# exp7lb.net
KiCad netlist of a schematic drawn in EasyEDA Pro
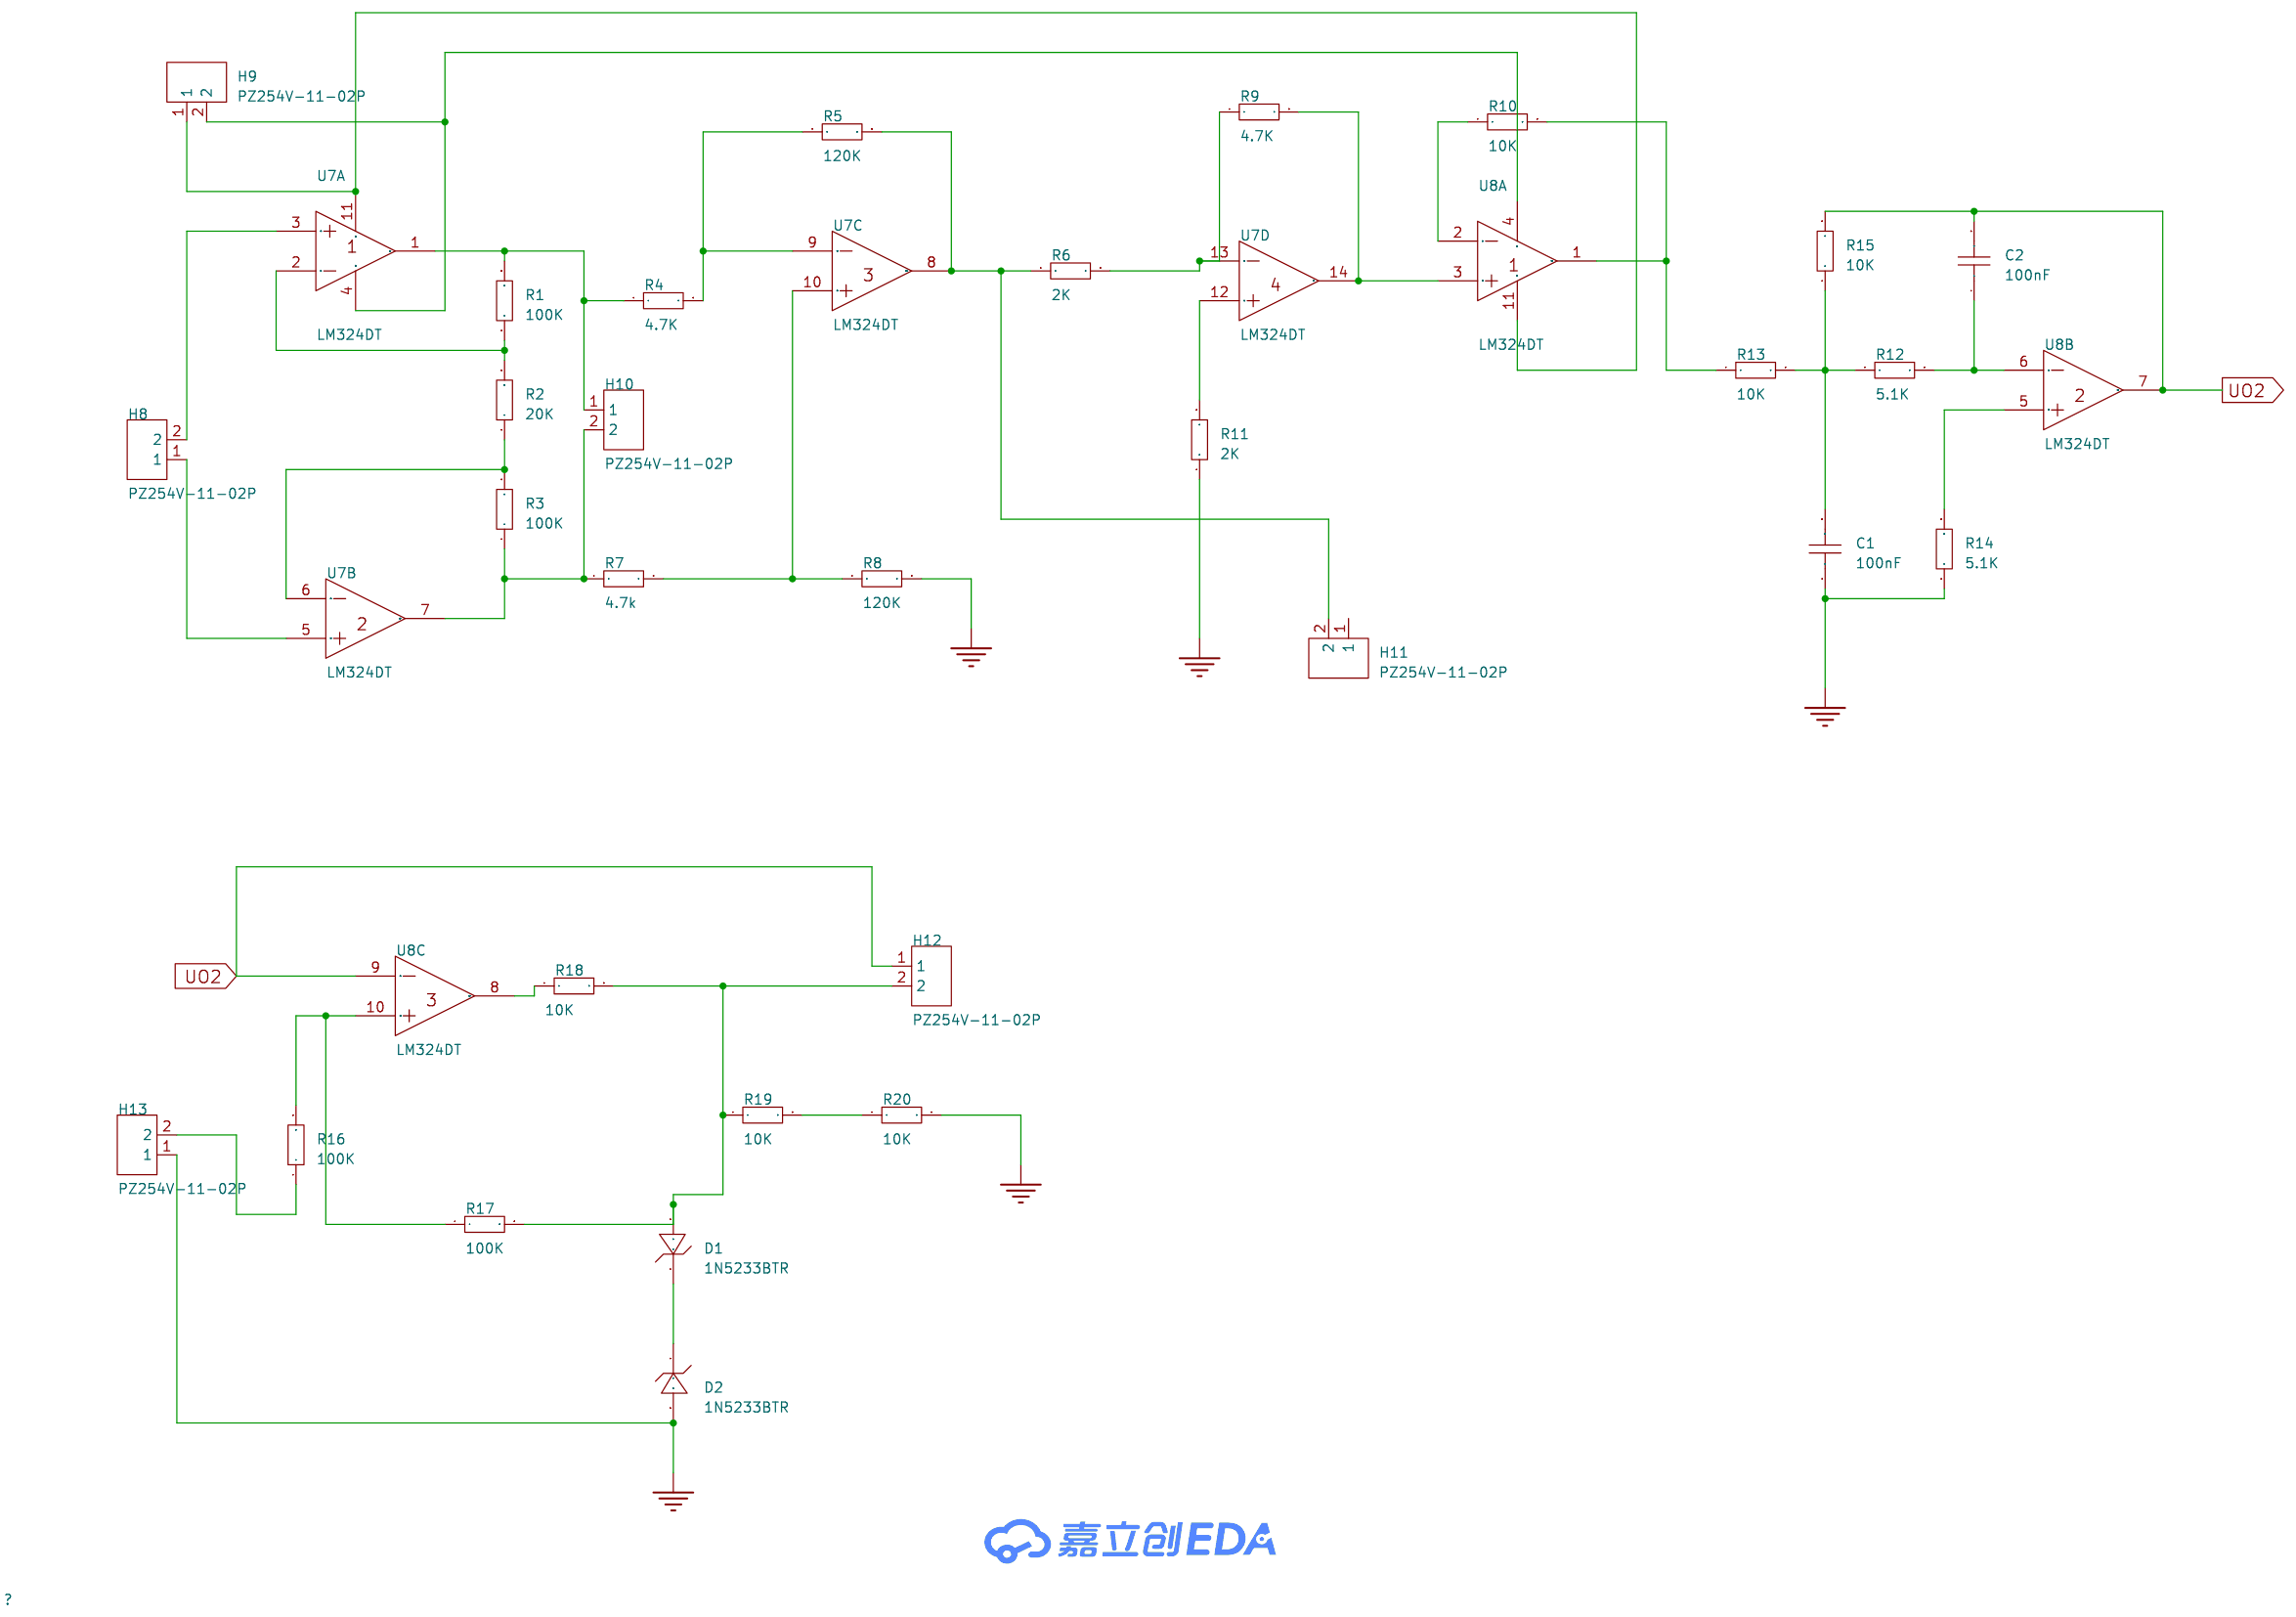
[diagram p0: schematic sheet]

(export (version "E")
  (design (tool "Eeschema 10.0.6"))
  (components
    (comp (ref "C1")
      (value "100nF")
      (footprint "easyedapro:C0603")
      (libsource (lib "easyedapro") (part "Capacitance"))
    )
    (comp (ref "C2")
      (value "100nF")
      (footprint "easyedapro:C0603")
      (libsource (lib "easyedapro") (part "Capacitance"))
    )
    (comp (ref "D1")
      (value "1N5233BTR")
      (footprint "easyedapro:DO-35_BD2.0-L4.2-P8.20-D0.5-RD")
      (description "二极管配置:独立式;稳压值(标称值):6V;稳压值(范围):5.7V~6.3V;耗散功率(Pd):500mW;")
      (fields (field (name "Manufacturer") "onsemi(安森美)"))
      (libsource (lib "easyedapro") (part "1N5233BTR"))
    )
    (comp (ref "D2")
      (value "1N5233BTR")
      (footprint "easyedapro:DO-35_BD2.0-L4.2-P8.20-D0.5-RD")
      (description "二极管配置:独立式;稳压值(标称值):6V;稳压值(范围):5.7V~6.3V;耗散功率(Pd):500mW;")
      (fields (field (name "Manufacturer") "onsemi(安森美)"))
      (libsource (lib "easyedapro") (part "1N5233BTR"))
    )
    (comp (ref "H8")
      (value "PZ254V-11-02P")
      (footprint "easyedapro:HDR-TH_2P-P2.54-V-M")
      (fields (field (name "Manufacturer") "XFCN(兴飞)"))
      (libsource (lib "easyedapro") (part "PZ254V-11-02P"))
    )
    (comp (ref "H9")
      (value "PZ254V-11-02P")
      (footprint "easyedapro:HDR-TH_2P-P2.54-V-M")
      (fields (field (name "Manufacturer") "XFCN(兴飞)"))
      (libsource (lib "easyedapro") (part "PZ254V-11-02P"))
    )
    (comp (ref "H10")
      (value "PZ254V-11-02P")
      (footprint "easyedapro:HDR-TH_2P-P2.54-V-M")
      (fields (field (name "Manufacturer") "XFCN(兴飞)"))
      (libsource (lib "easyedapro") (part "PZ254V-11-02P"))
    )
    (comp (ref "H11")
      (value "PZ254V-11-02P")
      (footprint "easyedapro:HDR-TH_2P-P2.54-V-M")
      (fields (field (name "Manufacturer") "XFCN(兴飞)"))
      (libsource (lib "easyedapro") (part "PZ254V-11-02P"))
    )
    (comp (ref "H12")
      (value "PZ254V-11-02P")
      (footprint "easyedapro:HDR-TH_2P-P2.54-V-M")
      (fields (field (name "Manufacturer") "XFCN(兴飞)"))
      (libsource (lib "easyedapro") (part "PZ254V-11-02P"))
    )
    (comp (ref "H13")
      (value "PZ254V-11-02P")
      (footprint "easyedapro:HDR-TH_2P-P2.54-V-M")
      (fields (field (name "Manufacturer") "XFCN(兴飞)"))
      (libsource (lib "easyedapro") (part "PZ254V-11-02P"))
    )
    (comp (ref "R1") (value "100K") (footprint "easyedapro:R0603") (libsource (lib "easyedapro") (part "电阻")))
    (comp (ref "R2") (value "20K") (footprint "easyedapro:R0603") (libsource (lib "easyedapro") (part "电阻")))
    (comp (ref "R3") (value "100K") (footprint "easyedapro:R0603") (libsource (lib "easyedapro") (part "电阻")))
    (comp (ref "R4") (value "4.7K") (footprint "easyedapro:R0603") (libsource (lib "easyedapro") (part "电阻")))
    (comp (ref "R5") (value "120K") (footprint "easyedapro:R0603") (libsource (lib "easyedapro") (part "电阻")))
    (comp (ref "R6") (value "2K") (footprint "easyedapro:R0603") (libsource (lib "easyedapro") (part "电阻")))
    (comp (ref "R7") (value "4.7k") (footprint "easyedapro:R0603") (libsource (lib "easyedapro") (part "电阻")))
    (comp (ref "R8") (value "120K") (footprint "easyedapro:R0603") (libsource (lib "easyedapro") (part "电阻")))
    (comp (ref "R9") (value "4.7K") (footprint "easyedapro:R0603") (libsource (lib "easyedapro") (part "电阻")))
    (comp (ref "R10") (value "10K") (footprint "easyedapro:R0603") (libsource (lib "easyedapro") (part "电阻")))
    (comp (ref "R11") (value "2K") (footprint "easyedapro:R0603") (libsource (lib "easyedapro") (part "电阻")))
    (comp (ref "R12")
      (value "5.1K")
      (footprint "easyedapro:R0603")
      (libsource (lib "easyedapro") (part "电阻"))
    )
    (comp (ref "R13") (value "10K") (footprint "easyedapro:R0603") (libsource (lib "easyedapro") (part "电阻")))
    (comp (ref "R14")
      (value "5.1K")
      (footprint "easyedapro:R0603")
      (libsource (lib "easyedapro") (part "电阻"))
    )
    (comp (ref "R15") (value "10K") (footprint "easyedapro:R0603") (libsource (lib "easyedapro") (part "电阻")))
    (comp (ref "R16")
      (value "100K")
      (footprint "easyedapro:R0603")
      (libsource (lib "easyedapro") (part "电阻"))
    )
    (comp (ref "R17")
      (value "100K")
      (footprint "easyedapro:R0603")
      (libsource (lib "easyedapro") (part "电阻"))
    )
    (comp (ref "R18") (value "10K") (footprint "easyedapro:R0603") (libsource (lib "easyedapro") (part "电阻")))
    (comp (ref "R19") (value "10K") (footprint "easyedapro:R0603") (libsource (lib "easyedapro") (part "电阻")))
    (comp (ref "R20") (value "10K") (footprint "easyedapro:R0603") (libsource (lib "easyedapro") (part "电阻")))
    (comp (ref "U7")
      (value "LM324DT")
      (footprint "easyedapro:SOIC-14_L8.7-W3.9-P1.27-LS6.0-BL")
      (description "放大器数:四路;轨到轨:-;增益带宽积(GBP):1.3MHz;输入失调电压(Vos):5mV;压摆率(SR):20V/us;输入偏置电流(Ib):300nA;")
      (fields (field (name "Manufacturer") "ST(意法半导体)"))
      (libsource (lib "easyedapro") (part "LM324DT"))
    )
    (comp (ref "U8")
      (value "LM324DT")
      (footprint "easyedapro:SOIC-14_L8.7-W3.9-P1.27-LS6.0-BL")
      (description "放大器数:四路;轨到轨:-;增益带宽积(GBP):1.3MHz;输入失调电压(Vos):5mV;压摆率(SR):20V/us;输入偏置电流(Ib):300nA;")
      (fields (field (name "Manufacturer") "ST(意法半导体)"))
      (libsource (lib "easyedapro") (part "LM324DT"))
    )
  )
  (nets
    (net (code "1") (name "GND") (class "Default")
      (node (ref "C1") (pin "1") (pinfunction "1_1") (pintype "input"))
      (node (ref "D2") (pin "2") (pinfunction "2_2") (pintype "unspecified"))
      (node (ref "H13") (pin "1") (pinfunction "1_1") (pintype "unspecified"))
      (node (ref "R11") (pin "1") (pinfunction "1_1") (pintype "input"))
      (node (ref "R14") (pin "1") (pinfunction "1_1") (pintype "input"))
      (node (ref "R20") (pin "2") (pinfunction "2_2") (pintype "input"))
      (node (ref "R8") (pin "2") (pinfunction "2_2") (pintype "input"))
    )
    (net (code "2") (name "Net-(C1-Pad2)") (class "Default")
      (node (ref "C1") (pin "2") (pinfunction "2_2") (pintype "input"))
      (node (ref "R12") (pin "1") (pinfunction "1_1") (pintype "input"))
      (node (ref "R13") (pin "2") (pinfunction "2_2") (pintype "input"))
      (node (ref "R15") (pin "1") (pinfunction "1_1") (pintype "input"))
    )
    (net (code "3") (name "Net-(D1-Pad1)") (class "Default")
      (node (ref "D1") (pin "1") (pinfunction "1_1") (pintype "unspecified"))
      (node (ref "D2") (pin "1") (pinfunction "1_1") (pintype "unspecified"))
    )
    (net (code "4") (name "Net-(D1-Pad2)") (class "Default")
      (node (ref "D1") (pin "2") (pinfunction "2_2") (pintype "unspecified"))
      (node (ref "H12") (pin "2") (pinfunction "2_2") (pintype "unspecified"))
      (node (ref "R17") (pin "2") (pinfunction "2_2") (pintype "input"))
      (node (ref "R18") (pin "2") (pinfunction "2_2") (pintype "input"))
      (node (ref "R19") (pin "1") (pinfunction "1_1") (pintype "input"))
    )
    (net (code "5") (name "Net-(H13-Pad2)") (class "Default")
      (node (ref "H13") (pin "2") (pinfunction "2_2") (pintype "unspecified"))
      (node (ref "R16") (pin "1") (pinfunction "1_1") (pintype "input"))
    )
    (net (code "6") (name "Net-(R19-Pad2)") (class "Default")
      (node (ref "R19") (pin "2") (pinfunction "2_2") (pintype "input"))
      (node (ref "R20") (pin "1") (pinfunction "1_1") (pintype "input"))
    )
    (net (code "7") (name "Net-(U7A-IN1+)") (class "Default")
      (node (ref "H8") (pin "2") (pinfunction "2_2") (pintype "unspecified"))
      (node (ref "U7") (pin "3") (pinfunction "IN1+_3") (pintype "unspecified"))
    )
    (net (code "8") (name "Net-(U7A-IN1-)") (class "Default")
      (node (ref "R1") (pin "1") (pinfunction "1_1") (pintype "input"))
      (node (ref "R2") (pin "2") (pinfunction "2_2") (pintype "input"))
      (node (ref "U7") (pin "2") (pinfunction "IN1-_2") (pintype "unspecified"))
    )
    (net (code "9") (name "Net-(U7A-OUT1)") (class "Default")
      (node (ref "H10") (pin "1") (pinfunction "1_1") (pintype "unspecified"))
      (node (ref "R1") (pin "2") (pinfunction "2_2") (pintype "input"))
      (node (ref "R4") (pin "1") (pinfunction "1_1") (pintype "input"))
      (node (ref "U7") (pin "1") (pinfunction "OUT1_1") (pintype "unspecified"))
    )
    (net (code "10") (name "Net-(U7A-VCC+)") (class "Default")
      (node (ref "H9") (pin "2") (pinfunction "2_2") (pintype "unspecified"))
      (node (ref "U7") (pin "4") (pinfunction "VCC+_4") (pintype "unspecified"))
      (node (ref "U8") (pin "4") (pinfunction "VCC+_4") (pintype "unspecified"))
    )
    (net (code "11") (name "Net-(U7A-VCC-)") (class "Default")
      (node (ref "H9") (pin "1") (pinfunction "1_1") (pintype "unspecified"))
      (node (ref "U7") (pin "11") (pinfunction "VCC-_11") (pintype "unspecified"))
      (node (ref "U8") (pin "11") (pinfunction "VCC-_11") (pintype "unspecified"))
    )
    (net (code "12") (name "Net-(U7B-IN2+)") (class "Default")
      (node (ref "H8") (pin "1") (pinfunction "1_1") (pintype "unspecified"))
      (node (ref "U7") (pin "5") (pinfunction "IN2+_5") (pintype "unspecified"))
    )
    (net (code "13") (name "Net-(U7B-IN2-)") (class "Default")
      (node (ref "R2") (pin "1") (pinfunction "1_1") (pintype "input"))
      (node (ref "R3") (pin "2") (pinfunction "2_2") (pintype "input"))
      (node (ref "U7") (pin "6") (pinfunction "IN2-_6") (pintype "unspecified"))
    )
    (net (code "14") (name "Net-(U7B-OUT2)") (class "Default")
      (node (ref "H10") (pin "2") (pinfunction "2_2") (pintype "unspecified"))
      (node (ref "R3") (pin "1") (pinfunction "1_1") (pintype "input"))
      (node (ref "R7") (pin "1") (pinfunction "1_1") (pintype "input"))
      (node (ref "U7") (pin "7") (pinfunction "OUT2_7") (pintype "unspecified"))
    )
    (net (code "15") (name "Net-(U7C-IN3+)") (class "Default")
      (node (ref "R7") (pin "2") (pinfunction "2_2") (pintype "input"))
      (node (ref "R8") (pin "1") (pinfunction "1_1") (pintype "input"))
      (node (ref "U7") (pin "10") (pinfunction "IN3+_10") (pintype "unspecified"))
    )
    (net (code "16") (name "Net-(U7C-IN3-)") (class "Default")
      (node (ref "R4") (pin "2") (pinfunction "2_2") (pintype "input"))
      (node (ref "R5") (pin "1") (pinfunction "1_1") (pintype "input"))
      (node (ref "U7") (pin "9") (pinfunction "IN3-_9") (pintype "unspecified"))
    )
    (net (code "17") (name "Net-(U7C-OUT3)") (class "Default")
      (node (ref "H11") (pin "2") (pinfunction "2_2") (pintype "unspecified"))
      (node (ref "R5") (pin "2") (pinfunction "2_2") (pintype "input"))
      (node (ref "R6") (pin "1") (pinfunction "1_1") (pintype "input"))
      (node (ref "U7") (pin "8") (pinfunction "OUT3_8") (pintype "unspecified"))
    )
    (net (code "18") (name "Net-(U7D-IN4+)") (class "Default")
      (node (ref "R11") (pin "2") (pinfunction "2_2") (pintype "input"))
      (node (ref "U7") (pin "12") (pinfunction "IN4+_12") (pintype "unspecified"))
    )
    (net (code "19") (name "Net-(U7D-IN4-)") (class "Default")
      (node (ref "R6") (pin "2") (pinfunction "2_2") (pintype "input"))
      (node (ref "R9") (pin "1") (pinfunction "1_1") (pintype "input"))
      (node (ref "U7") (pin "13") (pinfunction "IN4-_13") (pintype "unspecified"))
    )
    (net (code "20") (name "Net-(U7D-OUT4)") (class "Default")
      (node (ref "R9") (pin "2") (pinfunction "2_2") (pintype "input"))
      (node (ref "U7") (pin "14") (pinfunction "OUT4_14") (pintype "unspecified"))
      (node (ref "U8") (pin "3") (pinfunction "IN1+_3") (pintype "unspecified"))
    )
    (net (code "21") (name "Net-(U8A-IN1-)") (class "Default")
      (node (ref "R10") (pin "1") (pinfunction "1_1") (pintype "input"))
      (node (ref "U8") (pin "2") (pinfunction "IN1-_2") (pintype "unspecified"))
    )
    (net (code "22") (name "Net-(U8A-OUT1)") (class "Default")
      (node (ref "R10") (pin "2") (pinfunction "2_2") (pintype "input"))
      (node (ref "R13") (pin "1") (pinfunction "1_1") (pintype "input"))
      (node (ref "U8") (pin "1") (pinfunction "OUT1_1") (pintype "unspecified"))
    )
    (net (code "23") (name "Net-(U8B-IN2+)") (class "Default")
      (node (ref "R14") (pin "2") (pinfunction "2_2") (pintype "input"))
      (node (ref "U8") (pin "5") (pinfunction "IN2+_5") (pintype "unspecified"))
    )
    (net (code "24") (name "Net-(U8B-IN2-)") (class "Default")
      (node (ref "C2") (pin "1") (pinfunction "1_1") (pintype "input"))
      (node (ref "R12") (pin "2") (pinfunction "2_2") (pintype "input"))
      (node (ref "U8") (pin "6") (pinfunction "IN2-_6") (pintype "unspecified"))
    )
    (net (code "25") (name "Net-(U8C-IN3+)") (class "Default")
      (node (ref "R16") (pin "2") (pinfunction "2_2") (pintype "input"))
      (node (ref "R17") (pin "1") (pinfunction "1_1") (pintype "input"))
      (node (ref "U8") (pin "10") (pinfunction "IN3+_10") (pintype "unspecified"))
    )
    (net (code "26") (name "Net-(U8C-OUT3)") (class "Default")
      (node (ref "R18") (pin "1") (pinfunction "1_1") (pintype "input"))
      (node (ref "U8") (pin "8") (pinfunction "OUT3_8") (pintype "unspecified"))
    )
    (net (code "27") (name "UO2") (class "Default")
      (node (ref "C2") (pin "2") (pinfunction "2_2") (pintype "input"))
      (node (ref "H12") (pin "1") (pinfunction "1_1") (pintype "unspecified"))
      (node (ref "R15") (pin "2") (pinfunction "2_2") (pintype "input"))
      (node (ref "U8") (pin "7") (pinfunction "OUT2_7") (pintype "unspecified"))
      (node (ref "U8") (pin "9") (pinfunction "IN3-_9") (pintype "unspecified"))
    )
    (net (code "28") (name "unconnected-(H11-Pad1)") (class "Default")
      (node (ref "H11") (pin "1") (pinfunction "1_1") (pintype "unspecified"))
    )
  )
)
